# 06_Keypad.net
KiCad netlist of a schematic drawn in Altium Designer
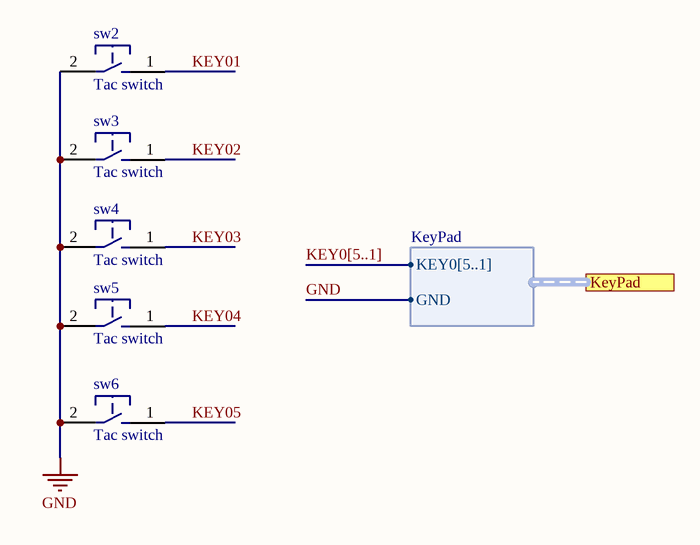
[diagram p0: [06] Keypad.SchDoc]

(export (version "E")
  (design (tool "Eeschema 10.0.6"))
  (components
    (comp (ref "sw2")
      (value "Tac switch")
      (footprint "MY_PB-SMD")
      (description "small tac switch")
      (fields (field (name "ASID PART NUMBER") "Tac switch-AS"))
      (libsource (lib "Mylib Rev 4") (part "Tac switch"))
    )
    (comp (ref "sw3")
      (value "Tac switch")
      (footprint "MY_PB-SMD")
      (description "small tac switch")
      (fields (field (name "ASID PART NUMBER") "Tac switch-AS"))
      (libsource (lib "Mylib Rev 4") (part "Tac switch"))
    )
    (comp (ref "sw4")
      (value "Tac switch")
      (footprint "MY_PB-SMD")
      (description "small tac switch")
      (fields (field (name "ASID PART NUMBER") "Tac switch-AS"))
      (libsource (lib "Mylib Rev 4") (part "Tac switch"))
    )
    (comp (ref "sw5")
      (value "Tac switch")
      (footprint "MY_PB-SMD")
      (description "small tac switch")
      (fields (field (name "ASID PART NUMBER") "Tac switch-AS"))
      (libsource (lib "Mylib Rev 4") (part "Tac switch"))
    )
    (comp (ref "sw6")
      (value "Tac switch")
      (footprint "MY_PB-SMD")
      (description "small tac switch")
      (fields (field (name "ASID PART NUMBER") "Tac switch-AS"))
      (libsource (lib "Mylib Rev 4") (part "Tac switch"))
    )
  )
  (nets
    (net (code "2") (name "/KEY01") (class "Default")
      (node (ref "sw2") (pin "1") (pinfunction "1_1") (pintype "passive"))
    )
    (net (code "3") (name "/KEY02") (class "Default")
      (node (ref "sw3") (pin "1") (pinfunction "1_1") (pintype "passive"))
    )
    (net (code "4") (name "/KEY03") (class "Default")
      (node (ref "sw4") (pin "1") (pinfunction "1_1") (pintype "passive"))
    )
    (net (code "5") (name "/KEY04") (class "Default")
      (node (ref "sw5") (pin "1") (pinfunction "1_1") (pintype "passive"))
    )
    (net (code "6") (name "/KEY05") (class "Default")
      (node (ref "sw6") (pin "1") (pinfunction "1_1") (pintype "passive"))
    )
    (net (code "9") (name "GND") (class "Default")
      (node (ref "sw2") (pin "2") (pinfunction "2_2") (pintype "passive"))
      (node (ref "sw3") (pin "2") (pinfunction "2_2") (pintype "passive"))
      (node (ref "sw4") (pin "2") (pinfunction "2_2") (pintype "passive"))
      (node (ref "sw5") (pin "2") (pinfunction "2_2") (pintype "passive"))
      (node (ref "sw6") (pin "2") (pinfunction "2_2") (pintype "passive"))
    )
  )
)
